# LEDs.net
KiCad netlist of a schematic drawn in Altium Designer
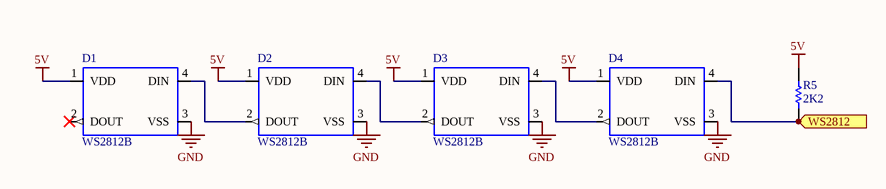
[diagram p0: LEDs.SchDoc]

(export (version "E")
  (design (tool "Eeschema 10.0.6"))
  (components
    (comp (ref "D1") (value "WS2812B") (footprint "WS2812B") (libsource (lib "Components") (part "WS2812B")))
    (comp (ref "D2") (value "WS2812B") (footprint "WS2812B") (libsource (lib "Components") (part "WS2812B")))
    (comp (ref "D3") (value "WS2812B") (footprint "WS2812B") (libsource (lib "Components") (part "WS2812B")))
    (comp (ref "D4") (value "WS2812B") (footprint "WS2812B") (libsource (lib "Components") (part "WS2812B")))
    (comp (ref "R5")
      (value "2K2")
      (footprint "R0402[1005]")
      (description "2K2 0.063W 1% 0402 (1005 Metric)")
      (fields (field (name "MANUFACTURER") "KOA Speer") (field (name "PARTNUMBER") "RK73H1ETTP2201F"))
      (libsource (lib "Resistors") (part "RES_2K2_0402_1%"))
    )
  )
  (nets
    (net (code "1") (name "/WS2812") (class "Default")
      (node (ref "D4") (pin "4") (pinfunction "DIN_4") (pintype "passive"))
      (node (ref "R5") (pin "1") (pinfunction "1_1") (pintype "passive"))
    )
    (net (code "2") (name "5V") (class "Default")
      (node (ref "D1") (pin "1") (pinfunction "VDD_1") (pintype "power_in"))
      (node (ref "D2") (pin "1") (pinfunction "VDD_1") (pintype "power_in"))
      (node (ref "D3") (pin "1") (pinfunction "VDD_1") (pintype "power_in"))
      (node (ref "D4") (pin "1") (pinfunction "VDD_1") (pintype "power_in"))
      (node (ref "R5") (pin "2") (pinfunction "2_2") (pintype "passive"))
    )
    (net (code "3") (name "GND") (class "Default")
      (node (ref "D1") (pin "3") (pinfunction "VSS_3") (pintype "power_in"))
      (node (ref "D2") (pin "3") (pinfunction "VSS_3") (pintype "power_in"))
      (node (ref "D3") (pin "3") (pinfunction "VSS_3") (pintype "power_in"))
      (node (ref "D4") (pin "3") (pinfunction "VSS_3") (pintype "power_in"))
    )
    (net (code "4") (name "Net-(D1-DIN)") (class "Default")
      (node (ref "D1") (pin "4") (pinfunction "DIN_4") (pintype "passive"))
      (node (ref "D2") (pin "2") (pinfunction "DOUT_2") (pintype "output"))
    )
    (net (code "5") (name "Net-(D2-DIN)") (class "Default")
      (node (ref "D2") (pin "4") (pinfunction "DIN_4") (pintype "passive"))
      (node (ref "D3") (pin "2") (pinfunction "DOUT_2") (pintype "output"))
    )
    (net (code "6") (name "Net-(D3-DIN)") (class "Default")
      (node (ref "D3") (pin "4") (pinfunction "DIN_4") (pintype "passive"))
      (node (ref "D4") (pin "2") (pinfunction "DOUT_2") (pintype "output"))
    )
    (net (code "7") (name "unconnected-(D1-DOUT-Pad2)") (class "Default")
      (node (ref "D1") (pin "2") (pinfunction "DOUT_2") (pintype "output+no_connect"))
    )
  )
)
